# Eleven.net
KiCad netlist of a schematic drawn in EAGLE
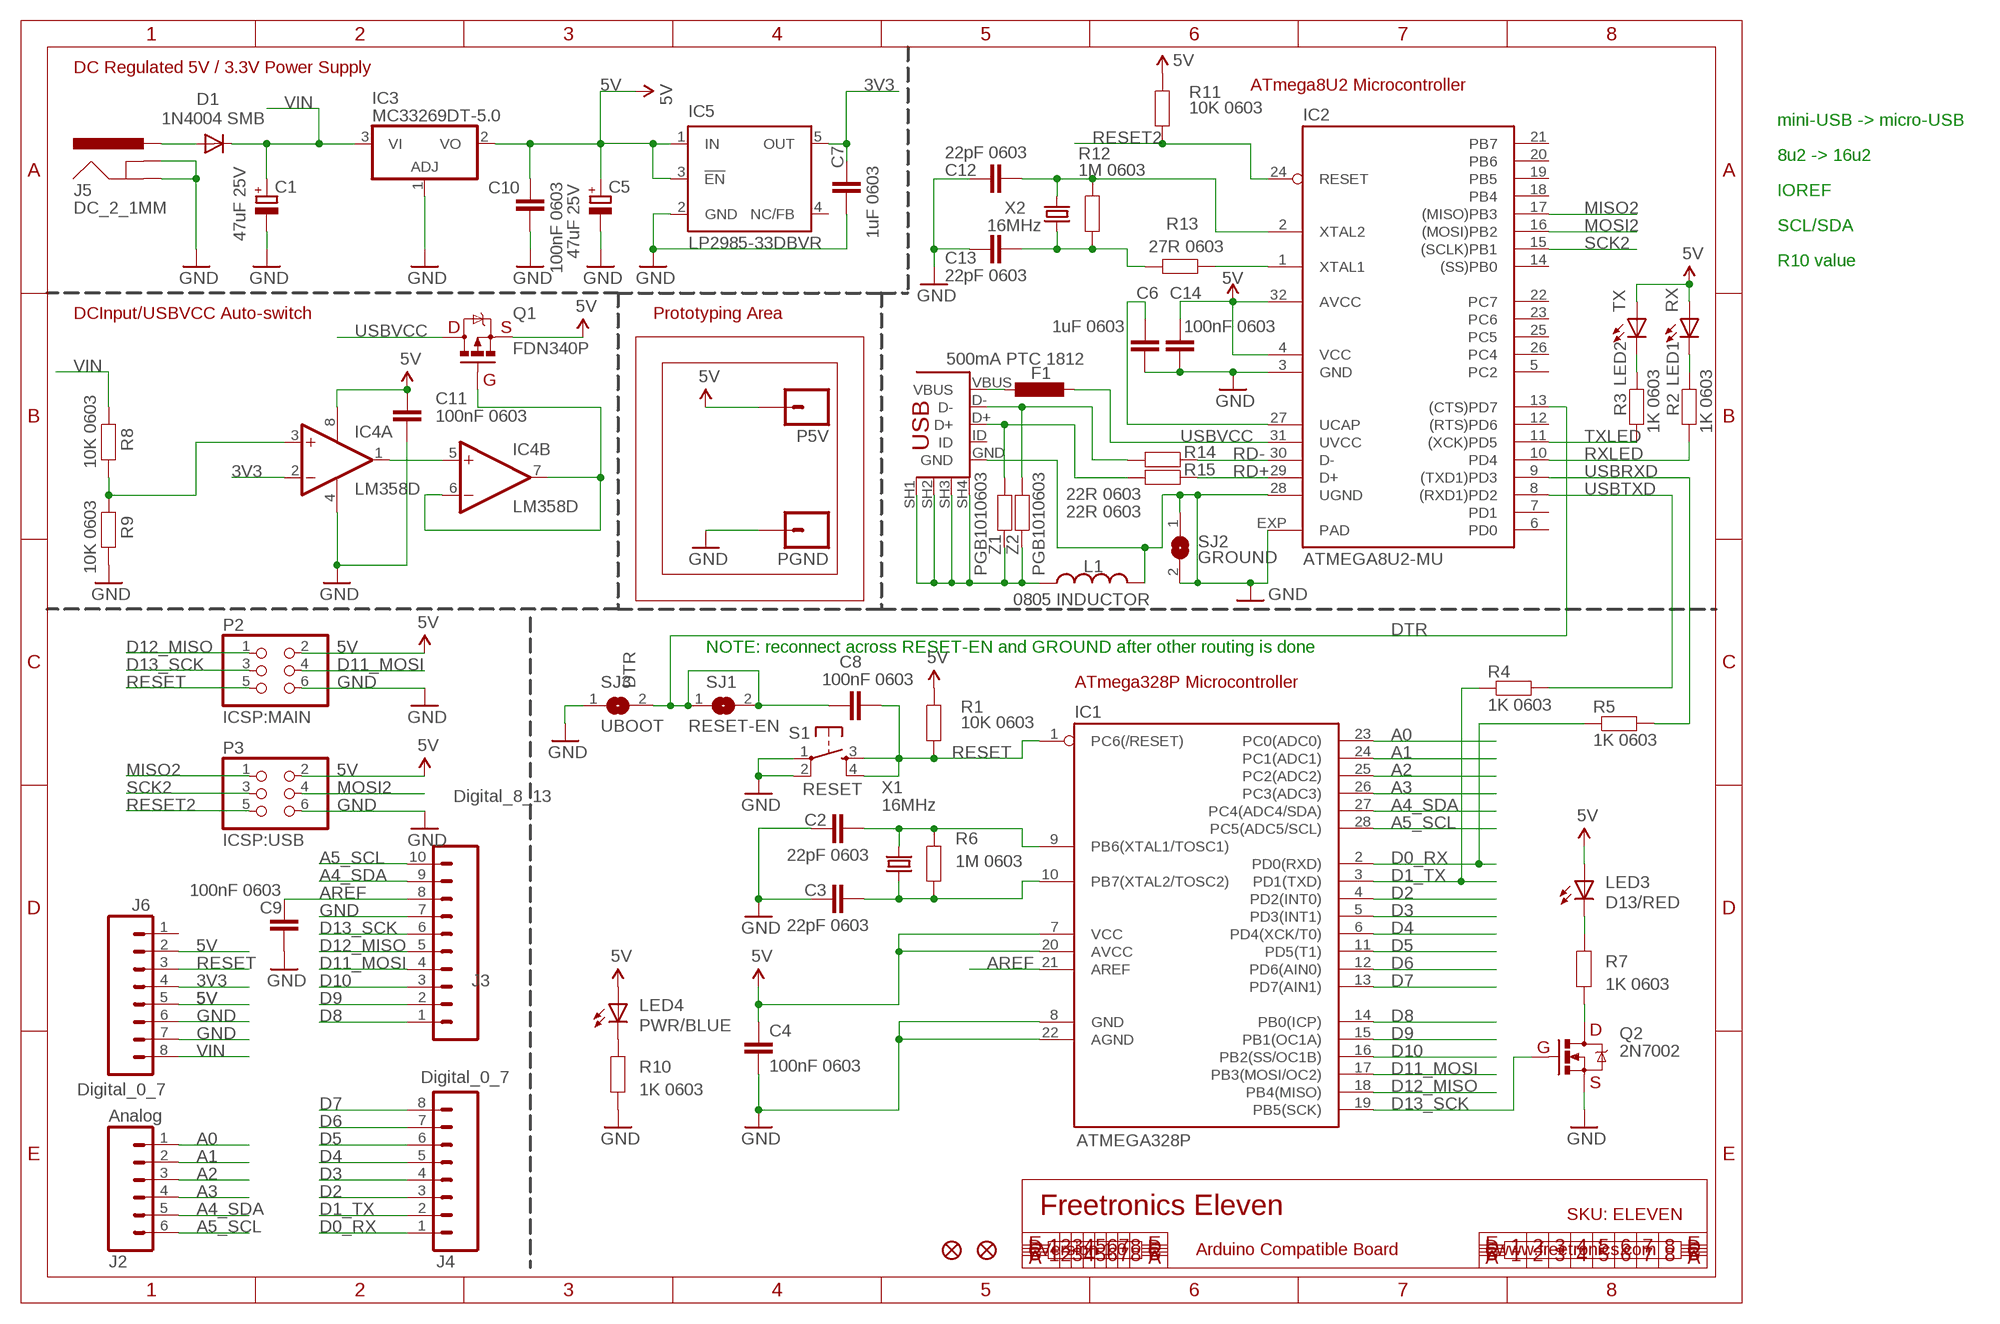
[diagram p0: schematic, sheet 1]

(export (version "E")
  (design (tool "Eeschema 10.0.6"))
  (components
    (comp (ref "C1")
      (value "47uF 25V")
      (footprint "eagle-import:PANASONIC_D")
      (libsource (lib "eagle-import") (part "CPOL-EUD"))
    )
    (comp (ref "C2")
      (value "22pF 0603")
      (footprint "eagle-import:0603")
      (libsource (lib "eagle-import") (part "CAP0603"))
    )
    (comp (ref "C3")
      (value "22pF 0603")
      (footprint "eagle-import:0603")
      (libsource (lib "eagle-import") (part "CAP0603"))
    )
    (comp (ref "C4")
      (value "100nF 0603")
      (footprint "eagle-import:0603")
      (libsource (lib "eagle-import") (part "CAP0603"))
    )
    (comp (ref "C5")
      (value "47uF 25V")
      (footprint "eagle-import:PANASONIC_D")
      (libsource (lib "eagle-import") (part "CPOL-EUD"))
    )
    (comp (ref "C6")
      (value "1uF 0603")
      (footprint "eagle-import:0603")
      (libsource (lib "eagle-import") (part "CAP0603"))
    )
    (comp (ref "C7")
      (value "1uF 0603")
      (footprint "eagle-import:0603")
      (libsource (lib "eagle-import") (part "CAP0603"))
    )
    (comp (ref "C8")
      (value "100nF 0603")
      (footprint "eagle-import:0603")
      (libsource (lib "eagle-import") (part "CAP0603"))
    )
    (comp (ref "C9")
      (value "100nF 0603")
      (footprint "eagle-import:0603")
      (libsource (lib "eagle-import") (part "CAP0603"))
    )
    (comp (ref "C10")
      (value "100nF 0603")
      (footprint "eagle-import:0603")
      (libsource (lib "eagle-import") (part "CAP0603"))
    )
    (comp (ref "C11")
      (value "100nF 0603")
      (footprint "eagle-import:0603")
      (libsource (lib "eagle-import") (part "CAP0603"))
    )
    (comp (ref "C12")
      (value "22pF 0603")
      (footprint "eagle-import:0603")
      (libsource (lib "eagle-import") (part "CAP0603"))
    )
    (comp (ref "C13")
      (value "22pF 0603")
      (footprint "eagle-import:0603")
      (libsource (lib "eagle-import") (part "CAP0603"))
    )
    (comp (ref "C14")
      (value "100nF 0603")
      (footprint "eagle-import:0603")
      (libsource (lib "eagle-import") (part "CAP0603"))
    )
    (comp (ref "D1")
      (value "1N4004 SMB")
      (footprint "eagle-import:SMB-DIODE")
      (libsource (lib "eagle-import") (part "DIODESMB"))
    )
    (comp (ref "F1")
      (value "500mA PTC 1812")
      (footprint "eagle-import:L1812")
      (libsource (lib "eagle-import") (part "L-EUL1812"))
    )
    (comp (ref "IC1")
      (value "ATMEGA328P")
      (footprint "eagle-import:DIL28-3")
      (libsource (lib "eagle-import") (part "AVR-MEGA8-P"))
    )
    (comp (ref "IC2")
      (value "ATMEGA8U2-MU")
      (footprint "eagle-import:ATMEL_QFN32")
      (libsource (lib "eagle-import") (part "ATMEL_ATMEGA8U2-MUQFN"))
    )
    (comp (ref "IC3")
      (value "MC33269DT-5.0")
      (footprint "eagle-import:DPACK")
      (libsource (lib "eagle-import") (part "MC33269?D-5.0"))
    )
    (comp (ref "IC4")
      (value "LM358D")
      (footprint "eagle-import:SO08")
      (libsource (lib "eagle-import") (part "LM358D"))
    )
    (comp (ref "IC5")
      (value "LP2985-33DBVR")
      (footprint "eagle-import:TEXAS_SOT23-DBV")
      (libsource (lib "eagle-import") (part "TEXAS_TPS77033"))
    )
    (comp (ref "J2")
      (value "Analog")
      (footprint "eagle-import:1X06")
      (libsource (lib "eagle-import") (part "M06SIP"))
    )
    (comp (ref "J3")
      (value "Digital_8_13")
      (footprint "eagle-import:1X10")
      (libsource (lib "eagle-import") (part "M100.1"))
    )
    (comp (ref "J4")
      (value "Digital_0_7")
      (footprint "eagle-import:1X08")
      (libsource (lib "eagle-import") (part "M08"))
    )
    (comp (ref "J5")
      (value "DC_2_1MM")
      (footprint "eagle-import:POWER_JACK_PTH")
      (libsource (lib "eagle-import") (part "POWER_JACKPTH"))
    )
    (comp (ref "J6")
      (value "Digital_0_7")
      (footprint "eagle-import:1X08")
      (libsource (lib "eagle-import") (part "M08"))
    )
    (comp (ref "L1")
      (value "0805 INDUCTOR")
      (footprint "eagle-import:0805-LARGE")
      (libsource (lib "eagle-import") (part "INDUCTOR0805-LARGE"))
    )
    (comp (ref "LED1")
      (value "RX")
      (footprint "eagle-import:LED-0603")
      (libsource (lib "eagle-import") (part "LED0603"))
    )
    (comp (ref "LED2")
      (value "TX")
      (footprint "eagle-import:LED-0603")
      (libsource (lib "eagle-import") (part "LED0603"))
    )
    (comp (ref "LED3")
      (value "D13/RED")
      (footprint "eagle-import:LED-0603")
      (libsource (lib "eagle-import") (part "LED0603"))
    )
    (comp (ref "LED4")
      (value "PWR/BLUE")
      (footprint "eagle-import:LED-0603")
      (libsource (lib "eagle-import") (part "LED0603"))
    )
    (comp (ref "P1")
      (value "USB-FT")
      (footprint "eagle-import:USB-MINIB-FT")
      (libsource (lib "eagle-import") (part "USB-FT"))
    )
    (comp (ref "P2")
      (value "ICSP:MAIN")
      (footprint "eagle-import:2X03")
      (libsource (lib "eagle-import") (part "PINHD-2X3"))
    )
    (comp (ref "P3")
      (value "ICSP:USB")
      (footprint "eagle-import:2X03")
      (libsource (lib "eagle-import") (part "PINHD-2X3"))
    )
    (comp (ref "P5V")
      (value "M01SMD")
      (footprint "eagle-import:LUXEON-PAD")
      (libsource (lib "eagle-import") (part "M01SMD"))
    )
    (comp (ref "PGND")
      (value "M01SMD")
      (footprint "eagle-import:LUXEON-PAD")
      (libsource (lib "eagle-import") (part "M01SMD"))
    )
    (comp (ref "Q1")
      (value "FDN340P")
      (footprint "eagle-import:SOT23")
      (libsource (lib "eagle-import") (part "MOSFET-PCHANNEL"))
    )
    (comp (ref "Q2")
      (value "2N7002")
      (footprint "eagle-import:SOT23-3")
      (libsource (lib "eagle-import") (part "MOSFET-NCHANNELSMD"))
    )
    (comp (ref "R1")
      (value "10K 0603")
      (footprint "eagle-import:0603")
      (libsource (lib "eagle-import") (part "RESISTOR0603"))
    )
    (comp (ref "R2")
      (value "1K 0603")
      (footprint "eagle-import:0603")
      (libsource (lib "eagle-import") (part "RESISTOR0603"))
    )
    (comp (ref "R3")
      (value "1K 0603")
      (footprint "eagle-import:0603")
      (libsource (lib "eagle-import") (part "RESISTOR0603"))
    )
    (comp (ref "R4")
      (value "1K 0603")
      (footprint "eagle-import:0603")
      (libsource (lib "eagle-import") (part "RESISTOR0603"))
    )
    (comp (ref "R5")
      (value "1K 0603")
      (footprint "eagle-import:0603")
      (libsource (lib "eagle-import") (part "RESISTOR0603"))
    )
    (comp (ref "R6")
      (value "1M 0603")
      (footprint "eagle-import:0603")
      (libsource (lib "eagle-import") (part "RESISTOR0603"))
    )
    (comp (ref "R7")
      (value "1K 0603")
      (footprint "eagle-import:0603")
      (libsource (lib "eagle-import") (part "RESISTOR0603"))
    )
    (comp (ref "R8")
      (value "10K 0603")
      (footprint "eagle-import:0603")
      (libsource (lib "eagle-import") (part "RESISTOR0603"))
    )
    (comp (ref "R9")
      (value "10K 0603")
      (footprint "eagle-import:0603")
      (libsource (lib "eagle-import") (part "RESISTOR0603"))
    )
    (comp (ref "R10")
      (value "1K 0603")
      (footprint "eagle-import:0603")
      (libsource (lib "eagle-import") (part "RESISTOR0603"))
    )
    (comp (ref "R11")
      (value "10K 0603")
      (footprint "eagle-import:0603")
      (libsource (lib "eagle-import") (part "RESISTOR0603"))
    )
    (comp (ref "R12")
      (value "1M 0603")
      (footprint "eagle-import:0603")
      (libsource (lib "eagle-import") (part "RESISTOR0603"))
    )
    (comp (ref "R13")
      (value "27R 0603")
      (footprint "eagle-import:0603")
      (libsource (lib "eagle-import") (part "RESISTOR0603"))
    )
    (comp (ref "R14")
      (value "22R 0603")
      (footprint "eagle-import:0603")
      (libsource (lib "eagle-import") (part "RESISTOR0603"))
    )
    (comp (ref "R15")
      (value "22R 0603")
      (footprint "eagle-import:0603")
      (libsource (lib "eagle-import") (part "RESISTOR0603"))
    )
    (comp (ref "S1")
      (value "RESET")
      (footprint "eagle-import:TACTILE_SWITCH_SMD")
      (libsource (lib "eagle-import") (part "TAC_SWITCHSMD"))
    )
    (comp (ref "SJ1")
      (value "RESET-EN")
      (footprint "eagle-import:SJ")
      (libsource (lib "eagle-import") (part "SJ"))
    )
    (comp (ref "SJ2")
      (value "GROUND")
      (footprint "eagle-import:SJ")
      (libsource (lib "eagle-import") (part "SJ"))
    )
    (comp (ref "SJ3")
      (value "UBOOT")
      (footprint "eagle-import:SJ")
      (libsource (lib "eagle-import") (part "SJ"))
    )
    (comp (ref "U$5")
      (value "FIDUCIAL1X2.5")
      (footprint "eagle-import:FIDUCIAL-1X2.5")
      (libsource (lib "eagle-import") (part "FIDUCIAL1X2.5"))
    )
    (comp (ref "U$14")
      (value "FIDUCIAL1X2.5")
      (footprint "eagle-import:FIDUCIAL-1X2.5")
      (libsource (lib "eagle-import") (part "FIDUCIAL1X2.5"))
    )
    (comp (ref "X1")
      (value "16MHz")
      (footprint "eagle-import:HC49U-V")
      (libsource (lib "eagle-import") (part "CRYSTALHC49UV"))
    )
    (comp (ref "X2")
      (value "16MHz")
      (footprint "eagle-import:HC49U-V")
      (libsource (lib "eagle-import") (part "CRYSTALHC49UV"))
    )
    (comp (ref "Z1")
      (value "PGB1010603")
      (footprint "eagle-import:0603")
      (libsource (lib "eagle-import") (part "RESISTOR0603"))
    )
    (comp (ref "Z2")
      (value "PGB1010603")
      (footprint "eagle-import:0603")
      (libsource (lib "eagle-import") (part "RESISTOR0603"))
    )
  )
  (nets
    (net (code "1") (name "/3V3") (class "Default")
      (node (ref "C7") (pin "2") (pinfunction "2_2") (pintype "passive"))
      (node (ref "IC4") (pin "2") (pinfunction "-IN_2") (pintype "input"))
      (node (ref "IC5") (pin "5") (pinfunction "OUT_5") (pintype "passive"))
      (node (ref "J6") (pin "4") (pinfunction "4_4") (pintype "passive"))
    )
    (net (code "2") (name "/A0") (class "Default")
      (node (ref "IC1") (pin "23") (pinfunction "PC0(ADC0)_23") (pintype "bidirectional"))
      (node (ref "J2") (pin "1") (pinfunction "1_1") (pintype "passive"))
    )
    (net (code "3") (name "/A1") (class "Default")
      (node (ref "IC1") (pin "24") (pinfunction "PC1(ADC1)_24") (pintype "bidirectional"))
      (node (ref "J2") (pin "2") (pinfunction "2_2") (pintype "passive"))
    )
    (net (code "4") (name "/A2") (class "Default")
      (node (ref "IC1") (pin "25") (pinfunction "PC2(ADC2)_25") (pintype "bidirectional"))
      (node (ref "J2") (pin "3") (pinfunction "3_3") (pintype "passive"))
    )
    (net (code "5") (name "/A3") (class "Default")
      (node (ref "IC1") (pin "26") (pinfunction "PC3(ADC3)_26") (pintype "bidirectional"))
      (node (ref "J2") (pin "4") (pinfunction "4_4") (pintype "passive"))
    )
    (net (code "6") (name "/A4_SDA") (class "Default")
      (node (ref "IC1") (pin "27") (pinfunction "PC4(ADC4/SDA)_27") (pintype "bidirectional"))
      (node (ref "J2") (pin "5") (pinfunction "5_5") (pintype "passive"))
      (node (ref "J3") (pin "9") (pinfunction "9_9") (pintype "passive"))
    )
    (net (code "7") (name "/A5_SCL") (class "Default")
      (node (ref "IC1") (pin "28") (pinfunction "PC5(ADC5/SCL)_28") (pintype "bidirectional"))
      (node (ref "J2") (pin "6") (pinfunction "6_6") (pintype "passive"))
      (node (ref "J3") (pin "10") (pinfunction "10_10") (pintype "passive"))
    )
    (net (code "8") (name "/AREF") (class "Default")
      (node (ref "C9") (pin "1") (pinfunction "1_1") (pintype "passive"))
      (node (ref "IC1") (pin "21") (pinfunction "AREF_21") (pintype "bidirectional"))
      (node (ref "J3") (pin "8") (pinfunction "8_8") (pintype "passive"))
    )
    (net (code "9") (name "/D0_RX") (class "Default")
      (node (ref "IC1") (pin "2") (pinfunction "PD0(RXD)_2") (pintype "bidirectional"))
      (node (ref "J4") (pin "1") (pinfunction "1_1") (pintype "passive"))
      (node (ref "R5") (pin "1") (pinfunction "1_1") (pintype "passive"))
    )
    (net (code "10") (name "/D1_TX") (class "Default")
      (node (ref "IC1") (pin "3") (pinfunction "PD1(TXD)_3") (pintype "bidirectional"))
      (node (ref "J4") (pin "2") (pinfunction "2_2") (pintype "passive"))
      (node (ref "R4") (pin "1") (pinfunction "1_1") (pintype "passive"))
    )
    (net (code "11") (name "/D2") (class "Default")
      (node (ref "IC1") (pin "4") (pinfunction "PD2(INT0)_4") (pintype "bidirectional"))
      (node (ref "J4") (pin "3") (pinfunction "3_3") (pintype "passive"))
    )
    (net (code "12") (name "/D3") (class "Default")
      (node (ref "IC1") (pin "5") (pinfunction "PD3(INT1)_5") (pintype "bidirectional"))
      (node (ref "J4") (pin "4") (pinfunction "4_4") (pintype "passive"))
    )
    (net (code "13") (name "/D4") (class "Default")
      (node (ref "IC1") (pin "6") (pinfunction "PD4(XCK/T0)_6") (pintype "bidirectional"))
      (node (ref "J4") (pin "5") (pinfunction "5_5") (pintype "passive"))
    )
    (net (code "14") (name "/D5") (class "Default")
      (node (ref "IC1") (pin "11") (pinfunction "PD5(T1)_11") (pintype "bidirectional"))
      (node (ref "J4") (pin "6") (pinfunction "6_6") (pintype "passive"))
    )
    (net (code "15") (name "/D6") (class "Default")
      (node (ref "IC1") (pin "12") (pinfunction "PD6(AIN0)_12") (pintype "bidirectional"))
      (node (ref "J4") (pin "7") (pinfunction "7_7") (pintype "passive"))
    )
    (net (code "16") (name "/D7") (class "Default")
      (node (ref "IC1") (pin "13") (pinfunction "PD7(AIN1)_13") (pintype "bidirectional"))
      (node (ref "J4") (pin "8") (pinfunction "8_8") (pintype "passive"))
    )
    (net (code "17") (name "/D8") (class "Default")
      (node (ref "IC1") (pin "14") (pinfunction "PB0(ICP)_14") (pintype "bidirectional"))
      (node (ref "J3") (pin "1") (pinfunction "1_1") (pintype "passive"))
    )
    (net (code "18") (name "/D9") (class "Default")
      (node (ref "IC1") (pin "15") (pinfunction "PB1(OC1A)_15") (pintype "bidirectional"))
      (node (ref "J3") (pin "2") (pinfunction "2_2") (pintype "passive"))
    )
    (net (code "19") (name "/D10") (class "Default")
      (node (ref "IC1") (pin "16") (pinfunction "PB2(SS/OC1B)_16") (pintype "bidirectional"))
      (node (ref "J3") (pin "3") (pinfunction "3_3") (pintype "passive"))
    )
    (net (code "20") (name "/D11_MOSI") (class "Default")
      (node (ref "IC1") (pin "17") (pinfunction "PB3(MOSI/OC2)_17") (pintype "bidirectional"))
      (node (ref "J3") (pin "4") (pinfunction "4_4") (pintype "passive"))
      (node (ref "P2") (pin "4") (pinfunction "4_4") (pintype "passive"))
    )
    (net (code "21") (name "/D12_MISO") (class "Default")
      (node (ref "IC1") (pin "18") (pinfunction "PB4(MISO)_18") (pintype "bidirectional"))
      (node (ref "J3") (pin "5") (pinfunction "5_5") (pintype "passive"))
      (node (ref "P2") (pin "1") (pinfunction "1_1") (pintype "passive"))
    )
    (net (code "22") (name "/D13_SCK") (class "Default")
      (node (ref "IC1") (pin "19") (pinfunction "PB5(SCK)_19") (pintype "bidirectional"))
      (node (ref "J3") (pin "6") (pinfunction "6_6") (pintype "passive"))
      (node (ref "P2") (pin "3") (pinfunction "3_3") (pintype "passive"))
      (node (ref "Q2") (pin "1") (pinfunction "G_1") (pintype "passive"))
    )
    (net (code "23") (name "/DTR") (class "Default")
      (node (ref "C8") (pin "1") (pinfunction "1_1") (pintype "passive"))
      (node (ref "IC2") (pin "13") (pinfunction "(CTS)PD7_13") (pintype "bidirectional"))
      (node (ref "SJ1") (pin "1") (pinfunction "1_1") (pintype "passive"))
      (node (ref "SJ1") (pin "2") (pinfunction "2_2") (pintype "passive"))
      (node (ref "SJ3") (pin "2") (pinfunction "2_2") (pintype "passive"))
    )
    (net (code "24") (name "/MISO2") (class "Default")
      (node (ref "IC2") (pin "17") (pinfunction "(MISO)PB3_17") (pintype "bidirectional"))
      (node (ref "P3") (pin "1") (pinfunction "1_1") (pintype "passive"))
    )
    (net (code "25") (name "/MOSI2") (class "Default")
      (node (ref "IC2") (pin "16") (pinfunction "(MOSI)PB2_16") (pintype "bidirectional"))
      (node (ref "P3") (pin "4") (pinfunction "4_4") (pintype "passive"))
    )
    (net (code "26") (name "/RD+") (class "Default")
      (node (ref "IC2") (pin "29") (pinfunction "D+_29") (pintype "bidirectional"))
      (node (ref "R15") (pin "1") (pinfunction "1_1") (pintype "passive"))
    )
    (net (code "27") (name "/RD-") (class "Default")
      (node (ref "IC2") (pin "30") (pinfunction "D-_30") (pintype "bidirectional"))
      (node (ref "R14") (pin "1") (pinfunction "1_1") (pintype "passive"))
    )
    (net (code "28") (name "/RESET") (class "Default")
      (node (ref "C8") (pin "2") (pinfunction "2_2") (pintype "passive"))
      (node (ref "IC1") (pin "1") (pinfunction "PC6(/RESET)_1") (pintype "bidirectional"))
      (node (ref "J6") (pin "3") (pinfunction "3_3") (pintype "passive"))
      (node (ref "P2") (pin "5") (pinfunction "5_5") (pintype "passive"))
      (node (ref "R1") (pin "1") (pinfunction "1_1") (pintype "passive"))
      (node (ref "S1") (pin "3") (pinfunction "3_3") (pintype "passive"))
      (node (ref "S1") (pin "4") (pinfunction "4_4") (pintype "passive"))
    )
    (net (code "29") (name "/RESET2") (class "Default")
      (node (ref "IC2") (pin "24") (pinfunction "RESET_24") (pintype "input"))
      (node (ref "P3") (pin "5") (pinfunction "5_5") (pintype "passive"))
      (node (ref "R11") (pin "1") (pinfunction "1_1") (pintype "passive"))
    )
    (net (code "30") (name "/RXLED") (class "Default")
      (node (ref "IC2") (pin "10") (pinfunction "PD4_10") (pintype "bidirectional"))
      (node (ref "R2") (pin "1") (pinfunction "1_1") (pintype "passive"))
    )
    (net (code "31") (name "/SCK2") (class "Default")
      (node (ref "IC2") (pin "15") (pinfunction "(SCLK)PB1_15") (pintype "bidirectional"))
      (node (ref "P3") (pin "3") (pinfunction "3_3") (pintype "passive"))
    )
    (net (code "32") (name "/TXLED") (class "Default")
      (node (ref "IC2") (pin "11") (pinfunction "(XCK)PD5_11") (pintype "bidirectional"))
      (node (ref "R3") (pin "1") (pinfunction "1_1") (pintype "passive"))
    )
    (net (code "33") (name "/USBRXD") (class "Default")
      (node (ref "IC2") (pin "9") (pinfunction "(TXD1)PD3_9") (pintype "bidirectional"))
      (node (ref "R5") (pin "2") (pinfunction "2_2") (pintype "passive"))
    )
    (net (code "34") (name "/USBTXD") (class "Default")
      (node (ref "IC2") (pin "8") (pinfunction "(RXD1)PD2_8") (pintype "bidirectional"))
      (node (ref "R4") (pin "2") (pinfunction "2_2") (pintype "passive"))
    )
    (net (code "35") (name "/USBVCC") (class "Default")
      (node (ref "F1") (pin "2") (pinfunction "2_2") (pintype "passive"))
      (node (ref "IC2") (pin "31") (pinfunction "UVCC_31") (pintype "power_in"))
      (node (ref "Q1") (pin "3") (pinfunction "D_3") (pintype "passive"))
    )
    (net (code "36") (name "/VIN") (class "Default")
      (node (ref "C1") (pin "+") (pinfunction "+_+") (pintype "passive"))
      (node (ref "D1") (pin "C") (pinfunction "C_C") (pintype "passive"))
      (node (ref "IC3") (pin "3") (pinfunction "VI_3") (pintype "input"))
      (node (ref "J6") (pin "8") (pinfunction "8_8") (pintype "passive"))
      (node (ref "R8") (pin "2") (pinfunction "2_2") (pintype "passive"))
    )
    (net (code "37") (name "5V") (class "Default")
      (node (ref "C10") (pin "1") (pinfunction "1_1") (pintype "passive"))
      (node (ref "C11") (pin "1") (pinfunction "1_1") (pintype "passive"))
      (node (ref "C14") (pin "1") (pinfunction "1_1") (pintype "passive"))
      (node (ref "C4") (pin "1") (pinfunction "1_1") (pintype "passive"))
      (node (ref "C5") (pin "+") (pinfunction "+_+") (pintype "passive"))
      (node (ref "IC1") (pin "20") (pinfunction "AVCC_20") (pintype "bidirectional"))
      (node (ref "IC1") (pin "7") (pinfunction "VCC_7") (pintype "bidirectional"))
      (node (ref "IC2") (pin "32") (pinfunction "AVCC_32") (pintype "power_in"))
      (node (ref "IC2") (pin "4") (pinfunction "VCC_4") (pintype "power_in"))
      (node (ref "IC3") (pin "2") (pinfunction "VO_2") (pintype "passive"))
      (node (ref "IC4") (pin "8") (pinfunction "V+_8") (pintype "power_in"))
      (node (ref "IC5") (pin "1") (pinfunction "IN_1") (pintype "input"))
      (node (ref "IC5") (pin "3") (pinfunction "~{EN}_3") (pintype "input"))
      (node (ref "J6") (pin "2") (pinfunction "2_2") (pintype "passive"))
      (node (ref "J6") (pin "5") (pinfunction "5_5") (pintype "passive"))
      (node (ref "LED1") (pin "A") (pinfunction "A_A") (pintype "passive"))
      (node (ref "LED2") (pin "A") (pinfunction "A_A") (pintype "passive"))
      (node (ref "LED3") (pin "A") (pinfunction "A_A") (pintype "passive"))
      (node (ref "LED4") (pin "A") (pinfunction "A_A") (pintype "passive"))
      (node (ref "P2") (pin "2") (pinfunction "2_2") (pintype "passive"))
      (node (ref "P3") (pin "2") (pinfunction "2_2") (pintype "passive"))
      (node (ref "P5V") (pin "P$1") (pinfunction "1_P$1") (pintype "passive"))
      (node (ref "Q1") (pin "2") (pinfunction "S_2") (pintype "passive"))
      (node (ref "R1") (pin "2") (pinfunction "2_2") (pintype "passive"))
      (node (ref "R11") (pin "2") (pinfunction "2_2") (pintype "passive"))
    )
    (net (code "38") (name "GND") (class "Default")
      (node (ref "C1") (pin "-") (pinfunction "-_-") (pintype "passive"))
      (node (ref "C10") (pin "2") (pinfunction "2_2") (pintype "passive"))
      (node (ref "C11") (pin "2") (pinfunction "2_2") (pintype "passive"))
      (node (ref "C12") (pin "1") (pinfunction "1_1") (pintype "passive"))
      (node (ref "C13") (pin "1") (pinfunction "1_1") (pintype "passive"))
      (node (ref "C14") (pin "2") (pinfunction "2_2") (pintype "passive"))
      (node (ref "C2") (pin "1") (pinfunction "1_1") (pintype "passive"))
      (node (ref "C3") (pin "1") (pinfunction "1_1") (pintype "passive"))
      (node (ref "C4") (pin "2") (pinfunction "2_2") (pintype "passive"))
      (node (ref "C5") (pin "-") (pinfunction "-_-") (pintype "passive"))
      (node (ref "C6") (pin "2") (pinfunction "2_2") (pintype "passive"))
      (node (ref "C7") (pin "1") (pinfunction "1_1") (pintype "passive"))
      (node (ref "C9") (pin "2") (pinfunction "2_2") (pintype "passive"))
      (node (ref "IC1") (pin "22") (pinfunction "AGND_22") (pintype "bidirectional"))
      (node (ref "IC1") (pin "8") (pinfunction "GND_8") (pintype "bidirectional"))
      (node (ref "IC2") (pin "28") (pinfunction "UGND_28") (pintype "power_in"))
      (node (ref "IC2") (pin "3") (pinfunction "GND_3") (pintype "power_in"))
      (node (ref "IC2") (pin "EXP") (pinfunction "PAD_EXP") (pintype "power_in"))
      (node (ref "IC3") (pin "1") (pinfunction "ADJ_1") (pintype "input"))
      (node (ref "IC4") (pin "4") (pinfunction "V-_4") (pintype "power_in"))
      (node (ref "IC5") (pin "2") (pinfunction "GND_2") (pintype "power_in"))
      (node (ref "J3") (pin "7") (pinfunction "7_7") (pintype "passive"))
      (node (ref "J5") (pin "GND") (pinfunction "GND_GND") (pintype "bidirectional"))
      (node (ref "J5") (pin "GNDBREAK") (pinfunction "GNDBREAK_GNDBREAK") (pintype "bidirectional"))
      (node (ref "J6") (pin "6") (pinfunction "6_6") (pintype "passive"))
      (node (ref "J6") (pin "7") (pinfunction "7_7") (pintype "passive"))
      (node (ref "L1") (pin "2") (pinfunction "2_2") (pintype "passive"))
      (node (ref "P1") (pin "GND") (pinfunction "GND_GND") (pintype "bidirectional"))
      (node (ref "P2") (pin "6") (pinfunction "6_6") (pintype "passive"))
      (node (ref "P3") (pin "6") (pinfunction "6_6") (pintype "passive"))
      (node (ref "PGND") (pin "P$1") (pinfunction "1_P$1") (pintype "passive"))
      (node (ref "Q2") (pin "2") (pinfunction "S_2") (pintype "passive"))
      (node (ref "R10") (pin "1") (pinfunction "1_1") (pintype "passive"))
      (node (ref "R9") (pin "1") (pinfunction "1_1") (pintype "passive"))
      (node (ref "S1") (pin "1") (pinfunction "1_1") (pintype "passive"))
      (node (ref "S1") (pin "2") (pinfunction "2_2") (pintype "passive"))
      (node (ref "SJ2") (pin "1") (pinfunction "1_1") (pintype "passive"))
      (node (ref "SJ2") (pin "2") (pinfunction "2_2") (pintype "passive"))
      (node (ref "SJ3") (pin "1") (pinfunction "1_1") (pintype "passive"))
    )
    (net (code "39") (name "Net-(C13-Pad2)") (class "Default")
      (node (ref "C13") (pin "2") (pinfunction "2_2") (pintype "passive"))
      (node (ref "R12") (pin "1") (pinfunction "1_1") (pintype "passive"))
      (node (ref "R13") (pin "2") (pinfunction "2_2") (pintype "passive"))
      (node (ref "X2") (pin "1") (pinfunction "1_1") (pintype "passive"))
    )
    (net (code "40") (name "Net-(D1-PadA)") (class "Default")
      (node (ref "D1") (pin "A") (pinfunction "A_A") (pintype "passive"))
      (node (ref "J5") (pin "PWR") (pinfunction "PWR_PWR") (pintype "bidirectional"))
    )
    (net (code "41") (name "Net-(F1-Pad1)") (class "Default")
      (node (ref "F1") (pin "1") (pinfunction "1_1") (pintype "passive"))
      (node (ref "P1") (pin "VBUS") (pinfunction "VBUS_VBUS") (pintype "bidirectional"))
    )
    (net (code "42") (name "Net-(IC1-PB6(XTAL1{slash}TOSC1))") (class "Default")
      (node (ref "C2") (pin "2") (pinfunction "2_2") (pintype "passive"))
      (node (ref "IC1") (pin "9") (pinfunction "PB6(XTAL1/TOSC1)_9") (pintype "bidirectional"))
      (node (ref "R6") (pin "2") (pinfunction "2_2") (pintype "passive"))
      (node (ref "X1") (pin "2") (pinfunction "2_2") (pintype "passive"))
    )
    (net (code "43") (name "Net-(IC1-PB7(XTAL2{slash}TOSC2))") (class "Default")
      (node (ref "C3") (pin "2") (pinfunction "2_2") (pintype "passive"))
      (node (ref "IC1") (pin "10") (pinfunction "PB7(XTAL2/TOSC2)_10") (pintype "bidirectional"))
      (node (ref "R6") (pin "1") (pinfunction "1_1") (pintype "passive"))
      (node (ref "X1") (pin "1") (pinfunction "1_1") (pintype "passive"))
    )
    (net (code "44") (name "Net-(IC2-UCAP)") (class "Default")
      (node (ref "C6") (pin "1") (pinfunction "1_1") (pintype "passive"))
      (node (ref "IC2") (pin "27") (pinfunction "UCAP_27") (pintype "passive"))
    )
    (net (code "45") (name "Net-(IC2-XTAL1)") (class "Default")
      (node (ref "IC2") (pin "1") (pinfunction "XTAL1_1") (pintype "bidirectional"))
      (node (ref "R13") (pin "1") (pinfunction "1_1") (pintype "passive"))
    )
    (net (code "46") (name "Net-(IC2-XTAL2)") (class "Default")
      (node (ref "C12") (pin "2") (pinfunction "2_2") (pintype "passive"))
      (node (ref "IC2") (pin "2") (pinfunction "XTAL2_2") (pintype "bidirectional"))
      (node (ref "R12") (pin "2") (pinfunction "2_2") (pintype "passive"))
      (node (ref "X2") (pin "2") (pinfunction "2_2") (pintype "passive"))
    )
    (net (code "47") (name "Net-(IC4A-+IN)") (class "Default")
      (node (ref "IC4") (pin "3") (pinfunction "+IN_3") (pintype "input"))
      (node (ref "R8") (pin "1") (pinfunction "1_1") (pintype "passive"))
      (node (ref "R9") (pin "2") (pinfunction "2_2") (pintype "passive"))
    )
    (net (code "48") (name "Net-(IC4A-OUT)") (class "Default")
      (node (ref "IC4") (pin "1") (pinfunction "OUT_1") (pintype "output"))
      (node (ref "IC4") (pin "5") (pinfunction "+IN_5") (pintype "input"))
    )
    (net (code "49") (name "Net-(IC4B--IN)") (class "Default")
      (node (ref "IC4") (pin "6") (pinfunction "-IN_6") (pintype "input"))
      (node (ref "IC4") (pin "7") (pinfunction "OUT_7") (pintype "output"))
      (node (ref "Q1") (pin "1") (pinfunction "G_1") (pintype "passive"))
    )
    (net (code "50") (name "Net-(LED1-PadC)") (class "Default")
      (node (ref "LED1") (pin "C") (pinfunction "C_C") (pintype "passive"))
      (node (ref "R2") (pin "2") (pinfunction "2_2") (pintype "passive"))
    )
    (net (code "51") (name "Net-(LED2-PadC)") (class "Default")
      (node (ref "LED2") (pin "C") (pinfunction "C_C") (pintype "passive"))
      (node (ref "R3") (pin "2") (pinfunction "2_2") (pintype "passive"))
    )
    (net (code "52") (name "Net-(LED3-PadC)") (class "Default")
      (node (ref "LED3") (pin "C") (pinfunction "C_C") (pintype "passive"))
      (node (ref "R7") (pin "2") (pinfunction "2_2") (pintype "passive"))
    )
    (net (code "53") (name "Net-(LED4-PadC)") (class "Default")
      (node (ref "LED4") (pin "C") (pinfunction "C_C") (pintype "passive"))
      (node (ref "R10") (pin "2") (pinfunction "2_2") (pintype "passive"))
    )
    (net (code "54") (name "Net-(P1-PadD+)") (class "Default")
      (node (ref "P1") (pin "D+") (pinfunction "D+_D+") (pintype "bidirectional"))
      (node (ref "R15") (pin "2") (pinfunction "2_2") (pintype "passive"))
      (node (ref "Z1") (pin "1") (pinfunction "1_1") (pintype "passive"))
    )
    (net (code "55") (name "Net-(P1-PadD-)") (class "Default")
      (node (ref "P1") (pin "D-") (pinfunction "D-_D-") (pintype "bidirectional"))
      (node (ref "R14") (pin "2") (pinfunction "2_2") (pintype "passive"))
      (node (ref "Z2") (pin "1") (pinfunction "1_1") (pintype "passive"))
    )
    (net (code "56") (name "Net-(P1-SH$1)") (class "Default")
      (node (ref "L1") (pin "1") (pinfunction "1_1") (pintype "passive"))
      (node (ref "P1") (pin "SH1") (pinfunction "SH$1_SH1") (pintype "passive"))
      (node (ref "P1") (pin "SH2") (pinfunction "SH$2_SH2") (pintype "passive"))
      (node (ref "P1") (pin "SH3") (pinfunction "SH$3_SH3") (pintype "passive"))
      (node (ref "P1") (pin "SH4") (pinfunction "SH$4_SH4") (pintype "passive"))
      (node (ref "Z1") (pin "2") (pinfunction "2_2") (pintype "passive"))
      (node (ref "Z2") (pin "2") (pinfunction "2_2") (pintype "passive"))
    )
    (net (code "57") (name "Net-(Q2-D)") (class "Default")
      (node (ref "Q2") (pin "3") (pinfunction "D_3") (pintype "passive"))
      (node (ref "R7") (pin "1") (pinfunction "1_1") (pintype "passive"))
    )
    (net (code "58") (name "unconnected-(IC2-(RTS)PD6-Pad12)") (class "Default")
      (node (ref "IC2") (pin "12") (pinfunction "(RTS)PD6_12") (pintype "bidirectional"))
    )
    (net (code "59") (name "unconnected-(IC2-(SS)PB0-Pad14)") (class "Default")
      (node (ref "IC2") (pin "14") (pinfunction "(SS)PB0_14") (pintype "bidirectional"))
    )
    (net (code "60") (name "unconnected-(IC2-PB4-Pad18)") (class "Default")
      (node (ref "IC2") (pin "18") (pinfunction "PB4_18") (pintype "bidirectional"))
    )
    (net (code "61") (name "unconnected-(IC2-PB5-Pad19)") (class "Default")
      (node (ref "IC2") (pin "19") (pinfunction "PB5_19") (pintype "bidirectional"))
    )
    (net (code "62") (name "unconnected-(IC2-PB6-Pad20)") (class "Default")
      (node (ref "IC2") (pin "20") (pinfunction "PB6_20") (pintype "bidirectional"))
    )
    (net (code "63") (name "unconnected-(IC2-PB7-Pad21)") (class "Default")
      (node (ref "IC2") (pin "21") (pinfunction "PB7_21") (pintype "bidirectional"))
    )
    (net (code "64") (name "unconnected-(IC2-PC2-Pad5)") (class "Default")
      (node (ref "IC2") (pin "5") (pinfunction "PC2_5") (pintype "bidirectional"))
    )
    (net (code "65") (name "unconnected-(IC2-PC4-Pad26)") (class "Default")
      (node (ref "IC2") (pin "26") (pinfunction "PC4_26") (pintype "bidirectional"))
    )
    (net (code "66") (name "unconnected-(IC2-PC5-Pad25)") (class "Default")
      (node (ref "IC2") (pin "25") (pinfunction "PC5_25") (pintype "bidirectional"))
    )
    (net (code "67") (name "unconnected-(IC2-PC6-Pad23)") (class "Default")
      (node (ref "IC2") (pin "23") (pinfunction "PC6_23") (pintype "bidirectional"))
    )
    (net (code "68") (name "unconnected-(IC2-PC7-Pad22)") (class "Default")
      (node (ref "IC2") (pin "22") (pinfunction "PC7_22") (pintype "bidirectional"))
    )
    (net (code "69") (name "unconnected-(IC2-PD0-Pad6)") (class "Default")
      (node (ref "IC2") (pin "6") (pinfunction "PD0_6") (pintype "bidirectional"))
    )
    (net (code "70") (name "unconnected-(IC2-PD1-Pad7)") (class "Default")
      (node (ref "IC2") (pin "7") (pinfunction "PD1_7") (pintype "bidirectional"))
    )
    (net (code "71") (name "unconnected-(IC5-NC{slash}FB-Pad4)") (class "Default")
      (node (ref "IC5") (pin "4") (pinfunction "NC/FB_4") (pintype "passive"))
    )
    (net (code "72") (name "unconnected-(J6-Pad1)") (class "Default")
      (node (ref "J6") (pin "1") (pinfunction "1_1") (pintype "passive"))
    )
    (net (code "73") (name "unconnected-(P1-PadID)") (class "Default")
      (node (ref "P1") (pin "ID") (pinfunction "ID_ID") (pintype "bidirectional"))
    )
  )
)
